# schematic.net
KiCad netlist of a schematic drawn in EasyEDA
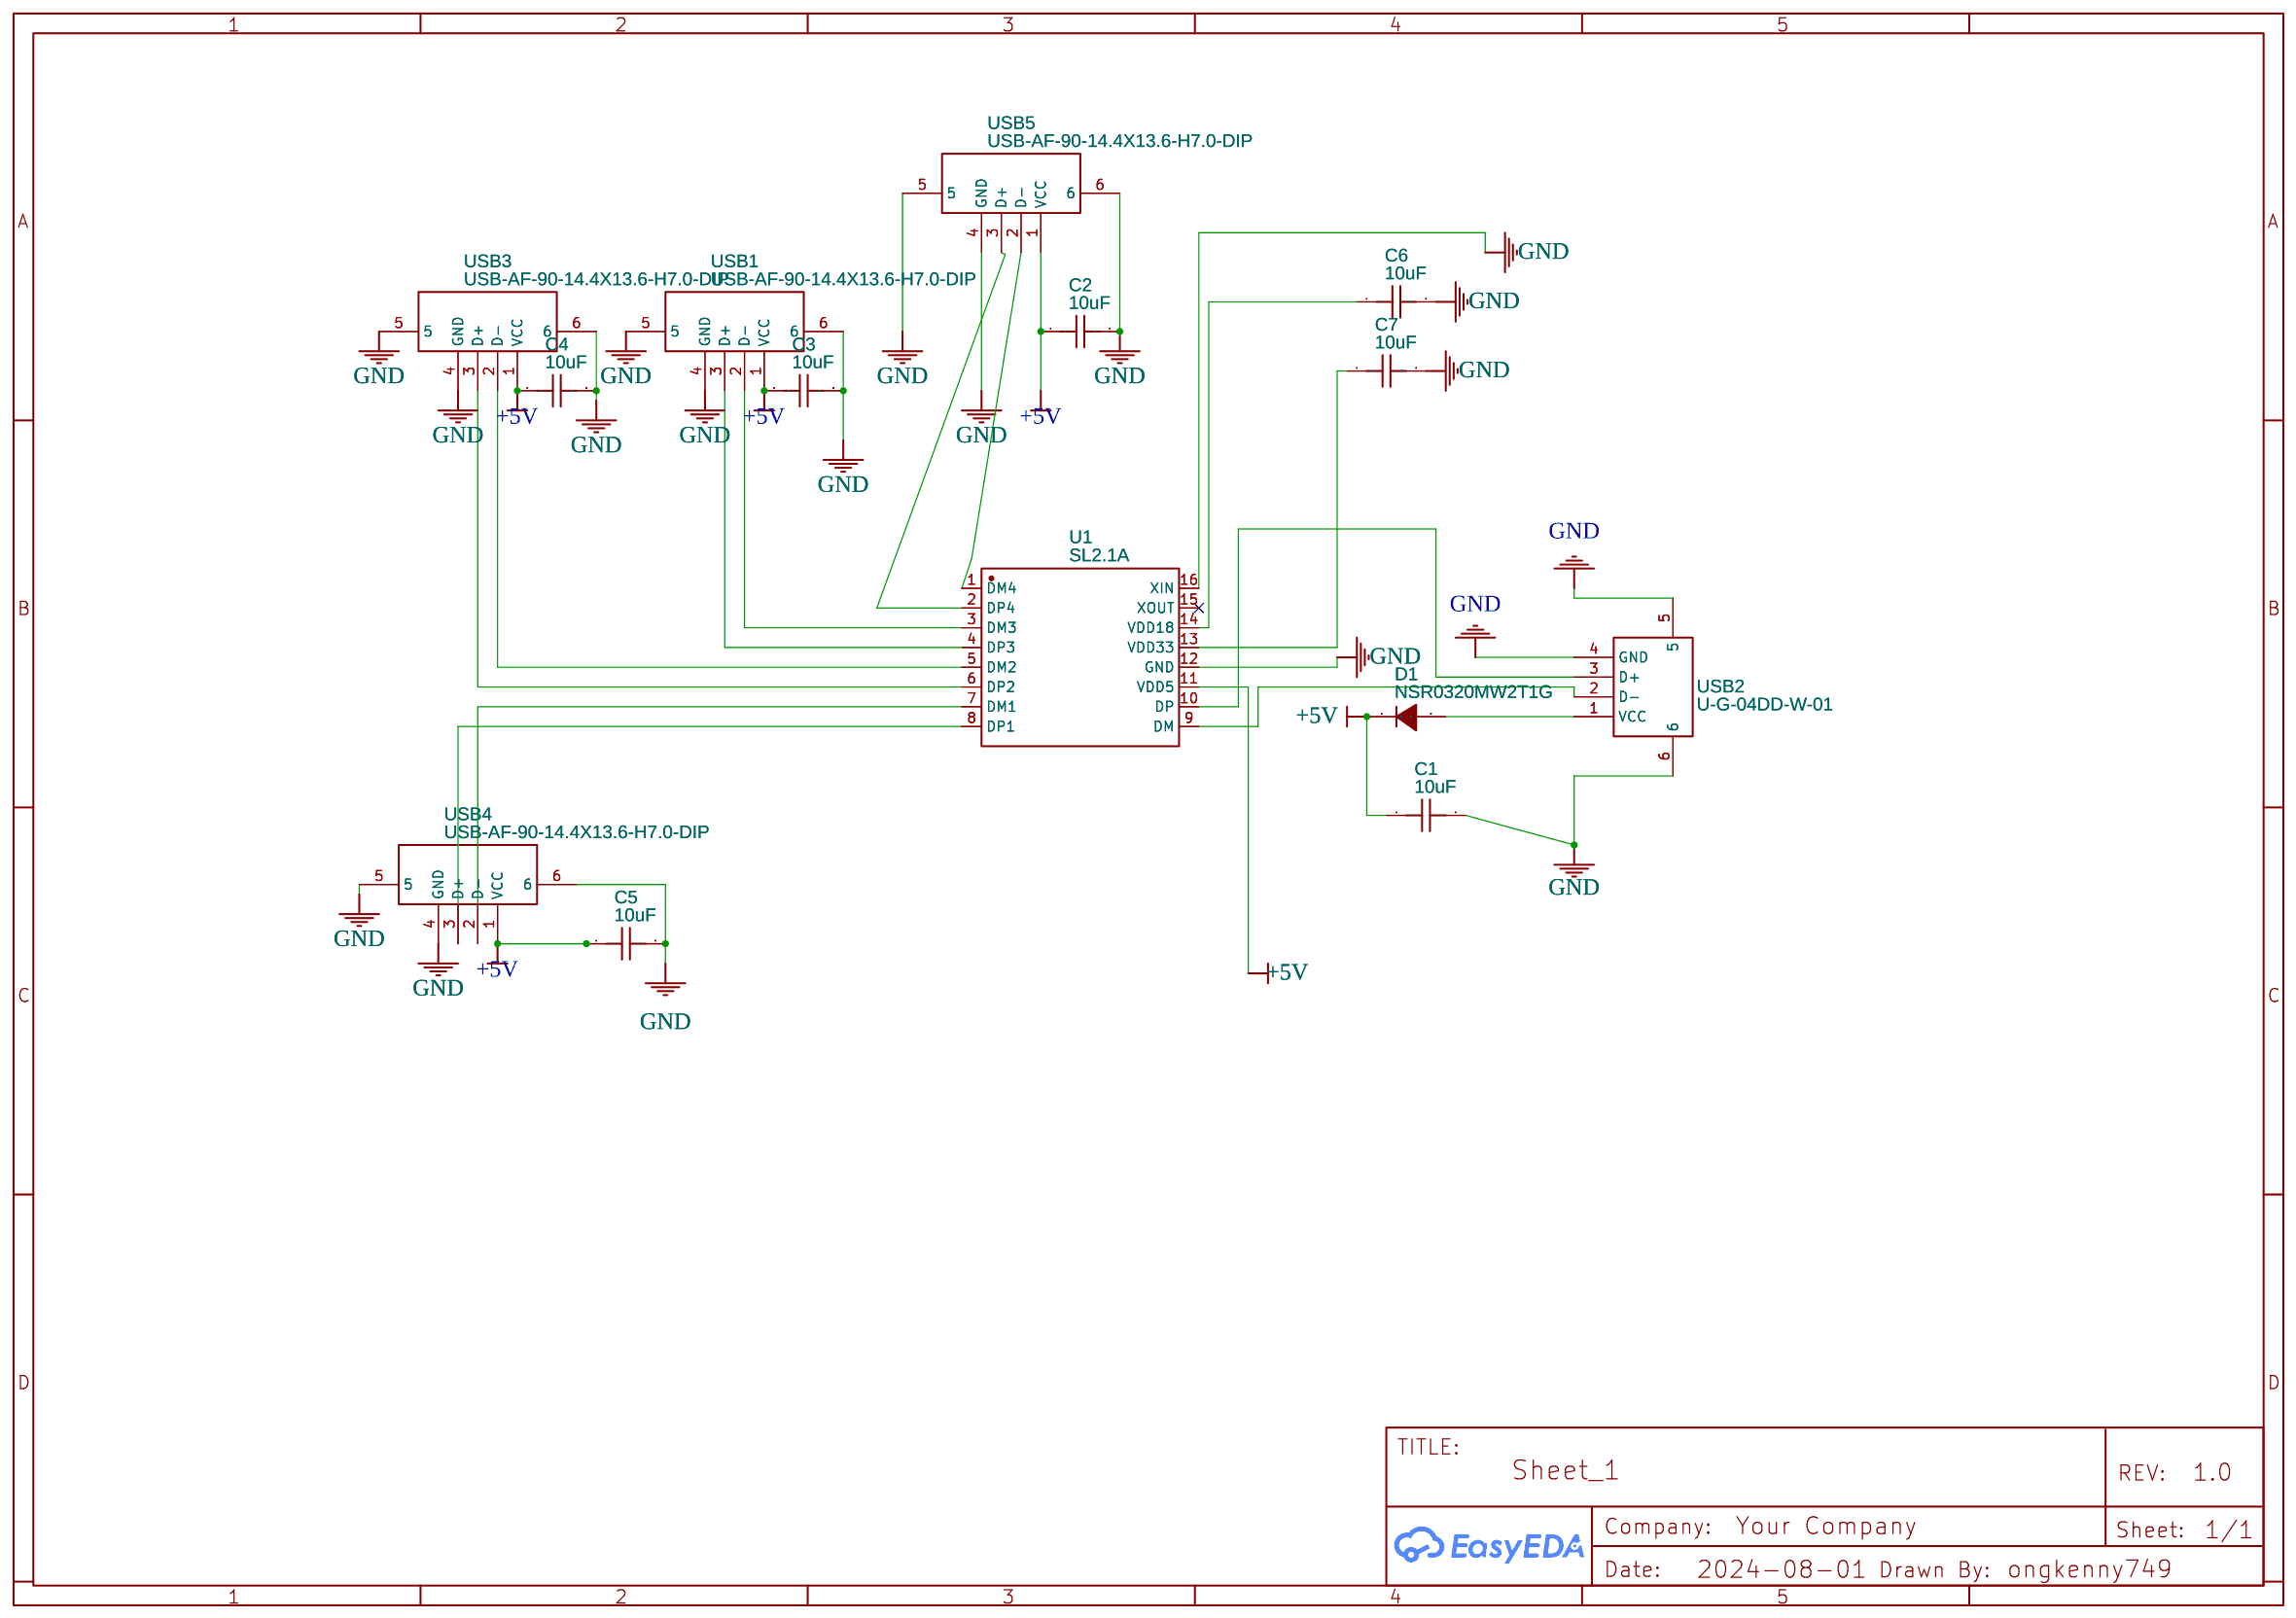
[diagram p0: schematic sheet]

(export (version "E")
  (design (tool "Eeschema 10.0.6"))
  (components
    (comp (ref "C1")
      (value "10uF")
      (fields
        (field (name "Manufacturer Part") "CL10A106KP8NNNC")
        (field (name "Manufacturer") "SAMSUNG(三星)")
      )
      (libsource (lib "") (part "CL10A106KP8NNNC"))
    )
    (comp (ref "C2")
      (value "10uF")
      (fields
        (field (name "Manufacturer Part") "CL10A106KP8NNNC")
        (field (name "Manufacturer") "SAMSUNG(三星)")
      )
      (libsource (lib "") (part "CL10A106KP8NNNC"))
    )
    (comp (ref "C3")
      (value "10uF")
      (fields
        (field (name "Manufacturer Part") "CL10A106KP8NNNC")
        (field (name "Manufacturer") "SAMSUNG(三星)")
      )
      (libsource (lib "") (part "CL10A106KP8NNNC"))
    )
    (comp (ref "C4")
      (value "10uF")
      (fields
        (field (name "Manufacturer Part") "CL10A106KP8NNNC")
        (field (name "Manufacturer") "SAMSUNG(三星)")
      )
      (libsource (lib "") (part "CL10A106KP8NNNC"))
    )
    (comp (ref "C5")
      (value "10uF")
      (fields
        (field (name "Manufacturer Part") "CL10A106KP8NNNC")
        (field (name "Manufacturer") "SAMSUNG(三星)")
      )
      (libsource (lib "") (part "CL10A106KP8NNNC"))
    )
    (comp (ref "C6")
      (value "10uF")
      (fields
        (field (name "Manufacturer Part") "CL10A106KP8NNNC")
        (field (name "Manufacturer") "SAMSUNG(三星)")
      )
      (libsource (lib "") (part "CL10A106KP8NNNC"))
    )
    (comp (ref "C7")
      (value "10uF")
      (fields
        (field (name "Manufacturer Part") "CL10A106KP8NNNC")
        (field (name "Manufacturer") "SAMSUNG(三星)")
      )
      (libsource (lib "") (part "CL10A106KP8NNNC"))
    )
    (comp (ref "D1")
      (value "NSR0320MW2T1G")
      (fields (field (name "Manufacturer") "onsemi(安森美)"))
      (libsource (lib "") (part "NSR0320MW2T1G"))
    )
    (comp (ref "U1")
      (value "SL2.1A")
      (fields (field (name "Manufacturer") "CoreChips(和芯润德)"))
      (libsource (lib "") (part "SL2.1A"))
    )
    (comp (ref "USB1")
      (value "USB-AF-90-14.4X13.6-H7.0-DIP")
      (fields (field (name "Manufacturer Part") "903-131A1011D10100") (field (name "Manufacturer") "精拓金"))
      (libsource (lib "") (part "USB-AF-90-14.4X13.6-H7.0-DIP"))
    )
    (comp (ref "USB2")
      (value "U-G-04DD-W-01")
      (fields (field (name "Manufacturer Part") "U-G-O4DD-W-1") (field (name "Manufacturer") "韩国韩荣"))
      (libsource (lib "") (part "U-G-04DD-W-01"))
    )
    (comp (ref "USB3")
      (value "USB-AF-90-14.4X13.6-H7.0-DIP")
      (fields (field (name "Manufacturer Part") "903-131A1011D10100") (field (name "Manufacturer") "精拓金"))
      (libsource (lib "") (part "USB-AF-90-14.4X13.6-H7.0-DIP"))
    )
    (comp (ref "USB4")
      (value "USB-AF-90-14.4X13.6-H7.0-DIP")
      (fields (field (name "Manufacturer Part") "903-131A1011D10100") (field (name "Manufacturer") "精拓金"))
      (libsource (lib "") (part "USB-AF-90-14.4X13.6-H7.0-DIP"))
    )
    (comp (ref "USB5")
      (value "USB-AF-90-14.4X13.6-H7.0-DIP")
      (fields (field (name "Manufacturer Part") "903-131A1011D10100") (field (name "Manufacturer") "精拓金"))
      (libsource (lib "") (part "USB-AF-90-14.4X13.6-H7.0-DIP"))
    )
  )
  (nets
    (net (code "1") (name "+5V") (class "Default")
      (node (ref "C1") (pin "1") (pinfunction "1_1") (pintype "unspecified"))
      (node (ref "C2") (pin "1") (pinfunction "1_1") (pintype "unspecified"))
      (node (ref "C3") (pin "1") (pinfunction "1_1") (pintype "unspecified"))
      (node (ref "C4") (pin "1") (pinfunction "1_1") (pintype "unspecified"))
      (node (ref "C5") (pin "1") (pinfunction "1_1") (pintype "unspecified"))
      (node (ref "D1") (pin "1") (pinfunction "C_1") (pintype "unspecified"))
      (node (ref "U1") (pin "11") (pinfunction "VDD5_11") (pintype "unspecified"))
      (node (ref "USB1") (pin "1") (pinfunction "VCC_1") (pintype "unspecified"))
      (node (ref "USB3") (pin "1") (pinfunction "VCC_1") (pintype "unspecified"))
      (node (ref "USB4") (pin "1") (pinfunction "VCC_1") (pintype "unspecified"))
      (node (ref "USB5") (pin "1") (pinfunction "VCC_1") (pintype "unspecified"))
    )
    (net (code "2") (name "GND") (class "Default")
      (node (ref "C1") (pin "2") (pinfunction "2_2") (pintype "unspecified"))
      (node (ref "C2") (pin "2") (pinfunction "2_2") (pintype "unspecified"))
      (node (ref "C3") (pin "2") (pinfunction "2_2") (pintype "unspecified"))
      (node (ref "C4") (pin "2") (pinfunction "2_2") (pintype "unspecified"))
      (node (ref "C5") (pin "2") (pinfunction "2_2") (pintype "unspecified"))
      (node (ref "C6") (pin "2") (pinfunction "2_2") (pintype "unspecified"))
      (node (ref "C7") (pin "2") (pinfunction "2_2") (pintype "unspecified"))
      (node (ref "U1") (pin "12") (pinfunction "GND_12") (pintype "unspecified"))
      (node (ref "U1") (pin "16") (pinfunction "XIN_16") (pintype "unspecified"))
      (node (ref "USB1") (pin "4") (pinfunction "GND_4") (pintype "unspecified"))
      (node (ref "USB1") (pin "5") (pinfunction "5_5") (pintype "unspecified"))
      (node (ref "USB1") (pin "6") (pinfunction "6_6") (pintype "unspecified"))
      (node (ref "USB2") (pin "4") (pinfunction "GND_4") (pintype "unspecified"))
      (node (ref "USB2") (pin "5") (pinfunction "5_5") (pintype "unspecified"))
      (node (ref "USB2") (pin "6") (pinfunction "6_6") (pintype "unspecified"))
      (node (ref "USB3") (pin "4") (pinfunction "GND_4") (pintype "unspecified"))
      (node (ref "USB3") (pin "5") (pinfunction "5_5") (pintype "unspecified"))
      (node (ref "USB3") (pin "6") (pinfunction "6_6") (pintype "unspecified"))
      (node (ref "USB4") (pin "4") (pinfunction "GND_4") (pintype "unspecified"))
      (node (ref "USB4") (pin "5") (pinfunction "5_5") (pintype "unspecified"))
      (node (ref "USB4") (pin "6") (pinfunction "6_6") (pintype "unspecified"))
      (node (ref "USB5") (pin "4") (pinfunction "GND_4") (pintype "unspecified"))
      (node (ref "USB5") (pin "5") (pinfunction "5_5") (pintype "unspecified"))
      (node (ref "USB5") (pin "6") (pinfunction "6_6") (pintype "unspecified"))
    )
    (net (code "3") (name "Net-(D1-A)") (class "Default")
      (node (ref "D1") (pin "2") (pinfunction "A_2") (pintype "unspecified"))
      (node (ref "USB2") (pin "1") (pinfunction "VCC_1") (pintype "unspecified"))
    )
    (net (code "4") (name "Net-(U1-DM)") (class "Default")
      (node (ref "U1") (pin "9") (pinfunction "DM_9") (pintype "unspecified"))
      (node (ref "USB2") (pin "2") (pinfunction "D-_2") (pintype "unspecified"))
    )
    (net (code "5") (name "Net-(U1-DM1)") (class "Default")
      (node (ref "U1") (pin "7") (pinfunction "DM1_7") (pintype "unspecified"))
      (node (ref "USB4") (pin "2") (pinfunction "D-_2") (pintype "unspecified"))
    )
    (net (code "6") (name "Net-(U1-DM2)") (class "Default")
      (node (ref "U1") (pin "5") (pinfunction "DM2_5") (pintype "unspecified"))
      (node (ref "USB3") (pin "2") (pinfunction "D-_2") (pintype "unspecified"))
    )
    (net (code "7") (name "Net-(U1-DM3)") (class "Default")
      (node (ref "U1") (pin "3") (pinfunction "DM3_3") (pintype "unspecified"))
      (node (ref "USB1") (pin "2") (pinfunction "D-_2") (pintype "unspecified"))
    )
    (net (code "8") (name "Net-(U1-DM4)") (class "Default")
      (node (ref "U1") (pin "1") (pinfunction "DM4_1") (pintype "unspecified"))
      (node (ref "USB5") (pin "2") (pinfunction "D-_2") (pintype "unspecified"))
    )
    (net (code "9") (name "Net-(U1-DP)") (class "Default")
      (node (ref "U1") (pin "10") (pinfunction "DP_10") (pintype "unspecified"))
      (node (ref "USB2") (pin "3") (pinfunction "D+_3") (pintype "unspecified"))
    )
    (net (code "10") (name "Net-(U1-DP1)") (class "Default")
      (node (ref "U1") (pin "8") (pinfunction "DP1_8") (pintype "unspecified"))
      (node (ref "USB4") (pin "3") (pinfunction "D+_3") (pintype "unspecified"))
    )
    (net (code "11") (name "Net-(U1-DP2)") (class "Default")
      (node (ref "U1") (pin "6") (pinfunction "DP2_6") (pintype "unspecified"))
      (node (ref "USB3") (pin "3") (pinfunction "D+_3") (pintype "unspecified"))
    )
    (net (code "12") (name "Net-(U1-DP3)") (class "Default")
      (node (ref "U1") (pin "4") (pinfunction "DP3_4") (pintype "unspecified"))
      (node (ref "USB1") (pin "3") (pinfunction "D+_3") (pintype "unspecified"))
    )
    (net (code "13") (name "Net-(U1-DP4)") (class "Default")
      (node (ref "U1") (pin "2") (pinfunction "DP4_2") (pintype "unspecified"))
      (node (ref "USB5") (pin "3") (pinfunction "D+_3") (pintype "unspecified"))
    )
    (net (code "14") (name "Net-(U1-VDD18)") (class "Default")
      (node (ref "C6") (pin "1") (pinfunction "1_1") (pintype "unspecified"))
      (node (ref "U1") (pin "14") (pinfunction "VDD18_14") (pintype "unspecified"))
    )
    (net (code "15") (name "Net-(U1-VDD33)") (class "Default")
      (node (ref "C7") (pin "1") (pinfunction "1_1") (pintype "unspecified"))
      (node (ref "U1") (pin "13") (pinfunction "VDD33_13") (pintype "unspecified"))
    )
    (net (code "16") (name "unconnected-(U1-XOUT-Pad15)") (class "Default")
      (node (ref "U1") (pin "15") (pinfunction "XOUT_15") (pintype "unspecified+no_connect"))
    )
  )
)
